# InputMicroproduct.net
KiCad netlist of a schematic drawn in Altium Designer
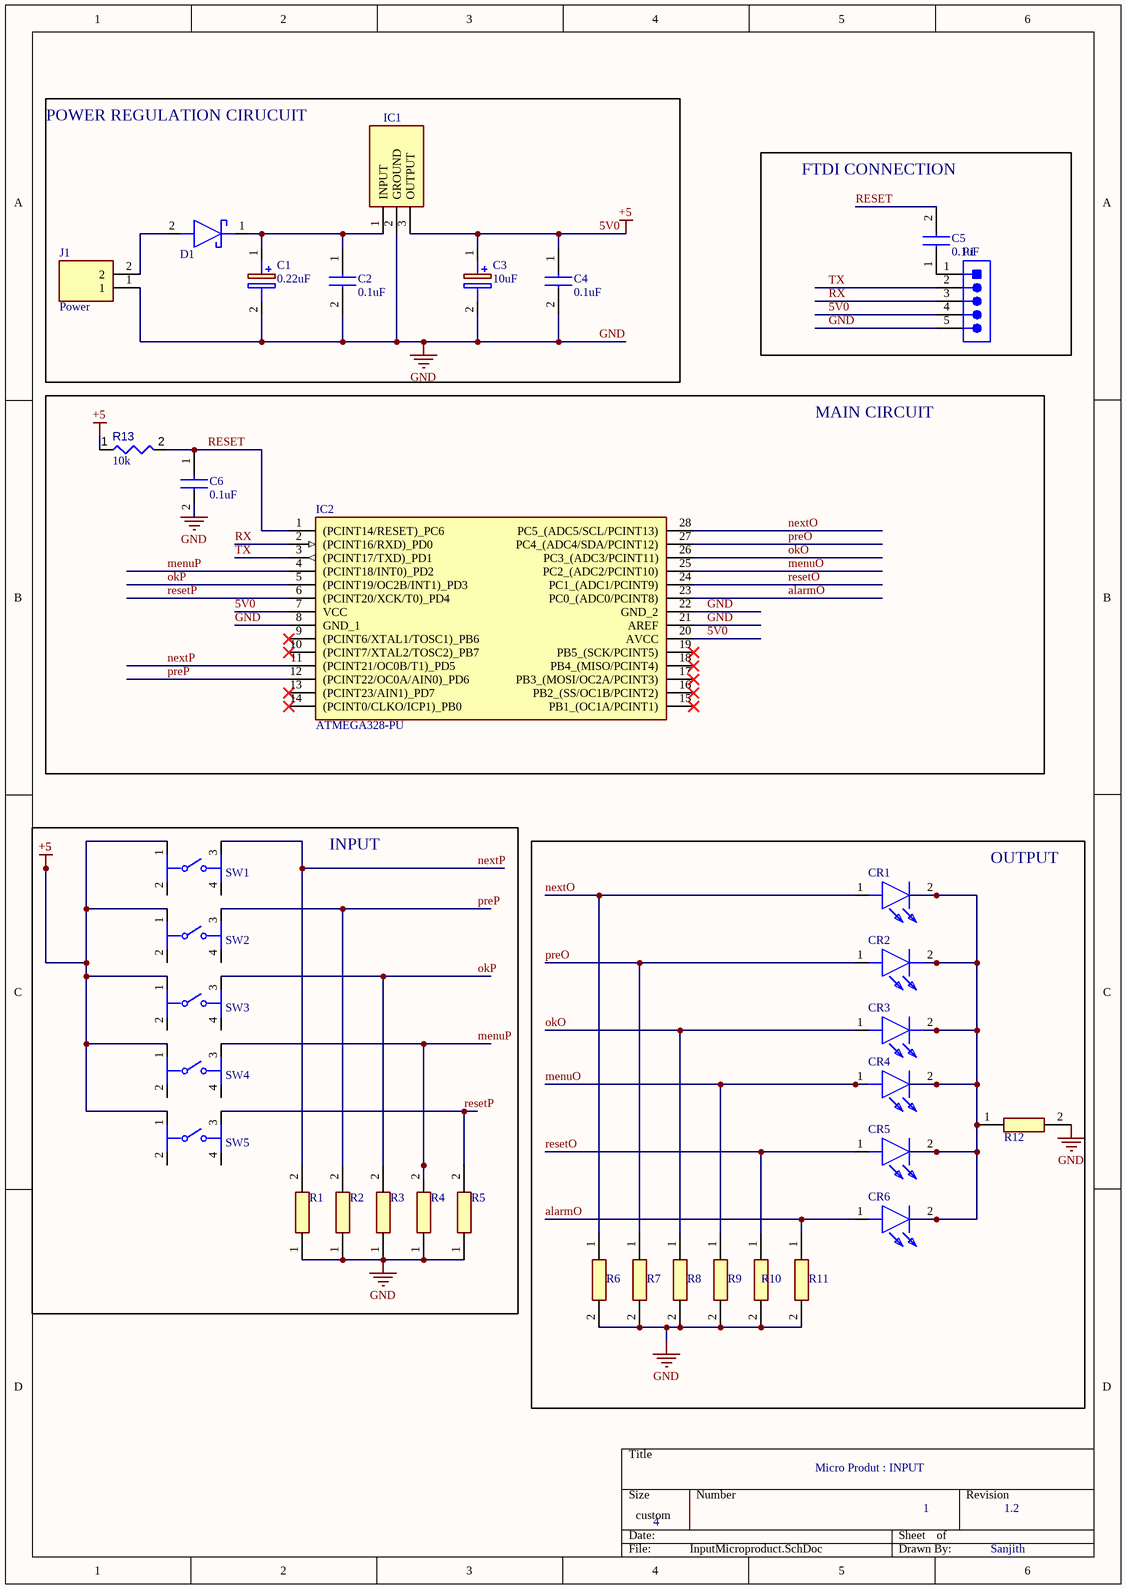
[diagram p0: InputMicroproduct.SchDoc]

(export (version "E")
  (design (tool "Eeschema 10.0.6"))
  (components
    (comp (ref "C1")
      (value "0.22uF")
      (footprint "SamacSys:CAPPRD200W52D500H1250")
      (description "Capacitor Polarised")
      (fields
        (field (name "MANUFACTURER_PART_NUMBER") "860010772002")
        (field (name "MOUSER PART NUMBER") "710-860010772002")
      )
      (libsource (lib "*") (part "860010772002"))
    )
    (comp (ref "C2")
      (value "0.1uF")
      (footprint "SamacSys:S104Z93Z5VL83L0R")
      (description "Capacitor")
      (fields
        (field (name "MANUFACTURER_PART_NUMBER") "S104Z93Z5VL83L0R")
        (field (name "MOUSER PART NUMBER") "594-S104Z93Z5VL83L0R")
      )
      (libsource (lib "*") (part "S104Z93Z5VL83L0R"))
    )
    (comp (ref "C3")
      (value "10uF")
      (footprint "SamacSys:CAPPRD200W55D500H1250")
      (description "Capacitor Polarised")
      (fields (field (name "MANUFACTURER_PART_NUMBER") "EEUFR1H100"))
      (libsource (lib "*") (part "EEUFR1H100"))
    )
    (comp (ref "C4")
      (value "0.1uF")
      (footprint "SamacSys:S104Z93Z5VL83L0R")
      (description "Capacitor")
      (fields
        (field (name "MANUFACTURER_PART_NUMBER") "S104Z93Z5VL83L0R")
        (field (name "MOUSER PART NUMBER") "594-S104Z93Z5VL83L0R")
      )
      (libsource (lib "*") (part "S104Z93Z5VL83L0R"))
    )
    (comp (ref "C5")
      (value "0.1uF")
      (footprint "SamacSys:S104Z93Z5VL83L0R")
      (description "Capacitor")
      (fields
        (field (name "MANUFACTURER_PART_NUMBER") "S104Z93Z5VL83L0R")
        (field (name "MOUSER PART NUMBER") "594-S104Z93Z5VL83L0R")
      )
      (libsource (lib "*") (part "S104Z93Z5VL83L0R"))
    )
    (comp (ref "C6")
      (value "0.1uF")
      (footprint "SamacSys:S104Z93Z5VL83L0R")
      (description "Capacitor")
      (fields
        (field (name "MANUFACTURER_PART_NUMBER") "S104Z93Z5VL83L0R")
        (field (name "MOUSER PART NUMBER") "594-S104Z93Z5VL83L0R")
      )
      (libsource (lib "*") (part "S104Z93Z5VL83L0R"))
    )
    (comp (ref "CR1")
      (value "SSL-LX5093SIC")
      (footprint "SamacSys:SSLLX5093SIC")
      (description "LED")
      (fields (field (name "MOUSER PART NUMBER") "696-SSL-LX5093SIC"))
      (libsource (lib "*") (part "SSL-LX5093SIC"))
    )
    (comp (ref "CR2")
      (value "SSL-LX5093SIC")
      (footprint "SamacSys:SSLLX5093SIC")
      (description "LED")
      (fields (field (name "MOUSER PART NUMBER") "696-SSL-LX5093SIC"))
      (libsource (lib "*") (part "SSL-LX5093SIC"))
    )
    (comp (ref "CR3")
      (value "SSL-LX5093SIC")
      (footprint "SamacSys:SSLLX5093SIC")
      (description "LED")
      (fields (field (name "MOUSER PART NUMBER") "696-SSL-LX5093SIC"))
      (libsource (lib "*") (part "SSL-LX5093SIC"))
    )
    (comp (ref "CR4")
      (value "SSL-LX5093SIC")
      (footprint "SamacSys:SSLLX5093SIC")
      (description "LED")
      (fields (field (name "MOUSER PART NUMBER") "696-SSL-LX5093SIC"))
      (libsource (lib "*") (part "SSL-LX5093SIC"))
    )
    (comp (ref "CR5")
      (value "SSL-LX5093SIC")
      (footprint "SamacSys:SSLLX5093SIC")
      (description "LED")
      (fields (field (name "MOUSER PART NUMBER") "696-SSL-LX5093SIC"))
      (libsource (lib "*") (part "SSL-LX5093SIC"))
    )
    (comp (ref "CR6")
      (value "SSL-LX5093SIC")
      (footprint "SamacSys:SSLLX5093SIC")
      (description "LED")
      (fields (field (name "MOUSER PART NUMBER") "696-SSL-LX5093SIC"))
      (libsource (lib "*") (part "SSL-LX5093SIC"))
    )
    (comp (ref "D1")
      (value "Protection Diode")
      (footprint "SamacSys:DIOAD950W60L350D150")
      (description "Schottky Diode")
      (fields
        (field (name "MANUFACTURER_PART_NUMBER") "SD103A-TR")
        (field (name "MOUSER PART NUMBER") "625-SD103A")
      )
      (libsource (lib "*") (part "SD103A-TR"))
    )
    (comp (ref "IC1")
      (value "Power Regulator")
      (footprint "SamacSys:TO255P460X1020X2008-3P")
      (description "Integrated Circuit")
      (fields
        (field (name "MANUFACTURER_PART_NUMBER") "L7805CV")
        (field (name "MOUSER PART NUMBER") "511-L7805CV")
      )
      (libsource (lib "*") (part "L7805CV"))
    )
    (comp (ref "IC2")
      (value "ATMEGA328-PU")
      (footprint "SamacSys:DIP1016W53P254L3468H457Q28N")
      (description "Integrated Circuit")
      (fields (field (name "MOUSER PART NUMBER") "556-ATMEGA328-PU"))
      (libsource (lib "*") (part "ATMEGA328-PU"))
    )
    (comp (ref "J1")
      (value "1546215-2")
      (footprint "SamacSys:15462152")
      (description "Connector - Two pin (Power)")
      (fields (field (name "MOUSER PART NUMBER") "571-1546215-2") (field (name "TEXT") "Power"))
      (libsource (lib "*") (part "1546215-2"))
    )
    (comp (ref "P1")
      (value "77311-462K05LF")
      (footprint "FCI-77311-5_V")
      (fields (field (name "MANUFACTURER") "FCI Electronics"))
      (libsource (lib "University of Moratuwa") (part "CN-1P-M-R5"))
    )
    (comp (ref "R1")
      (value "CFR-25JB-52-1K2")
      (footprint "SamacSys:RESAD1590W60L630D240")
      (description "Pulldown Resistor")
      (fields (field (name "MOUSER PART NUMBER") "603-CFR-25JB-52-1K2"))
      (libsource (lib "") (part "CFR-25JB-52-1K2_1"))
    )
    (comp (ref "R2")
      (value "CFR-25JB-52-1K2")
      (footprint "SamacSys:RESAD1590W60L630D240")
      (description "Pulldown Resistor")
      (fields (field (name "MOUSER PART NUMBER") "603-CFR-25JB-52-1K2"))
      (libsource (lib "") (part "CFR-25JB-52-1K2_1"))
    )
    (comp (ref "R3")
      (value "CFR-25JB-52-1K2")
      (footprint "SamacSys:RESAD1590W60L630D240")
      (description "Pulldown Resistor")
      (fields (field (name "MOUSER PART NUMBER") "603-CFR-25JB-52-1K2"))
      (libsource (lib "") (part "CFR-25JB-52-1K2_1"))
    )
    (comp (ref "R4")
      (value "CFR-25JB-52-1K2")
      (footprint "SamacSys:RESAD1590W60L630D240")
      (description "Pulldown Resistor")
      (fields (field (name "MOUSER PART NUMBER") "603-CFR-25JB-52-1K2"))
      (libsource (lib "") (part "CFR-25JB-52-1K2_1"))
    )
    (comp (ref "R5")
      (value "CFR-25JB-52-1K2")
      (footprint "SamacSys:RESAD1590W60L630D240")
      (description "Pulldown Resistor")
      (fields (field (name "MOUSER PART NUMBER") "603-CFR-25JB-52-1K2"))
      (libsource (lib "") (part "CFR-25JB-52-1K2_1"))
    )
    (comp (ref "R6")
      (value "CFR-25JB-52-1K2")
      (footprint "SamacSys:RESAD1590W60L630D240")
      (description "Pulldown Resistor")
      (fields (field (name "MOUSER PART NUMBER") "603-CFR-25JB-52-1K2"))
      (libsource (lib "*") (part "CFR-25JB-52-1K2"))
    )
    (comp (ref "R7")
      (value "CFR-25JB-52-1K2")
      (footprint "SamacSys:RESAD1590W60L630D240")
      (description "Pulldown Resistor")
      (fields (field (name "MOUSER PART NUMBER") "603-CFR-25JB-52-1K2"))
      (libsource (lib "*") (part "CFR-25JB-52-1K2"))
    )
    (comp (ref "R8")
      (value "CFR-25JB-52-1K2")
      (footprint "SamacSys:RESAD1590W60L630D240")
      (description "Pulldown Resistor")
      (fields (field (name "MOUSER PART NUMBER") "603-CFR-25JB-52-1K2"))
      (libsource (lib "*") (part "CFR-25JB-52-1K2"))
    )
    (comp (ref "R9")
      (value "CFR-25JB-52-1K2")
      (footprint "SamacSys:RESAD1590W60L630D240")
      (description "Pulldown Resistor")
      (fields (field (name "MOUSER PART NUMBER") "603-CFR-25JB-52-1K2"))
      (libsource (lib "*") (part "CFR-25JB-52-1K2"))
    )
    (comp (ref "R10")
      (value "CFR-25JB-52-1K2")
      (footprint "SamacSys:RESAD1590W60L630D240")
      (description "Pulldown Resistor")
      (fields (field (name "MOUSER PART NUMBER") "603-CFR-25JB-52-1K2"))
      (libsource (lib "*") (part "CFR-25JB-52-1K2"))
    )
    (comp (ref "R11")
      (value "CFR-25JB-52-1K2")
      (footprint "SamacSys:RESAD1590W60L630D240")
      (description "Pulldown Resistor")
      (fields (field (name "MOUSER PART NUMBER") "603-CFR-25JB-52-1K2"))
      (libsource (lib "*") (part "CFR-25JB-52-1K2"))
    )
    (comp (ref "R12")
      (value "CFR-25JB-52-1K2")
      (footprint "SamacSys:RESAD1590W60L630D240")
      (description "Pulldown Resistor")
      (fields (field (name "MOUSER PART NUMBER") "603-CFR-25JB-52-1K2"))
      (libsource (lib "") (part "CFR-25JB-52-1K2_2"))
    )
    (comp (ref "R13")
      (value "10k")
      (footprint "RESA60-630X240")
      (description "Axial Resistor, 10 KOhm, +/- 1%, 0.25 W, -55 to 155 degC, 2-Pin THD, RoHS, Bulk")
      (fields (field (name "POWER") "250mW") (field (name "MANUFACTURER") "Yageo"))
      (libsource (lib "University of Moratuwa") (part "RES-2"))
    )
    (comp (ref "SW1")
      (value "3-1825910-1")
      (footprint "FP-3-1825910-1-MFG")
      (description "Switch Tactile OFF (ON) SPST Round Button PC Pins 0.05A 24VDC 100000Cycles 1.57N Thru-Hole")
      (fields (field (name "MANUFACTURER") "TE Connectivity"))
      (libsource (lib "Altium Content Vault") (part "b8895f3f4cefb76e1819d2863dba89b"))
    )
    (comp (ref "SW2")
      (value "3-1825910-1")
      (footprint "FP-3-1825910-1-MFG")
      (description "Switch Tactile OFF (ON) SPST Round Button PC Pins 0.05A 24VDC 100000Cycles 1.57N Thru-Hole")
      (fields (field (name "MANUFACTURER") "TE Connectivity"))
      (libsource (lib "Altium Content Vault") (part "b8895f3f4cefb76e1819d2863dba89b"))
    )
    (comp (ref "SW3")
      (value "3-1825910-1")
      (footprint "FP-3-1825910-1-MFG")
      (description "Switch Tactile OFF (ON) SPST Round Button PC Pins 0.05A 24VDC 100000Cycles 1.57N Thru-Hole")
      (fields (field (name "MANUFACTURER") "TE Connectivity"))
      (libsource (lib "Altium Content Vault") (part "b8895f3f4cefb76e1819d2863dba89b"))
    )
    (comp (ref "SW4")
      (value "3-1825910-1")
      (footprint "FP-3-1825910-1-MFG")
      (description "Switch Tactile OFF (ON) SPST Round Button PC Pins 0.05A 24VDC 100000Cycles 1.57N Thru-Hole")
      (fields (field (name "MANUFACTURER") "TE Connectivity"))
      (libsource (lib "Altium Content Vault") (part "b8895f3f4cefb76e1819d2863dba89b"))
    )
    (comp (ref "SW5")
      (value "3-1825910-1")
      (footprint "FP-3-1825910-1-MFG")
      (description "Switch Tactile OFF (ON) SPST Round Button PC Pins 0.05A 24VDC 100000Cycles 1.57N Thru-Hole")
      (fields (field (name "MANUFACTURER") "TE Connectivity"))
      (libsource (lib "Altium Content Vault") (part "b8895f3f4cefb76e1819d2863dba89b"))
    )
  )
  (nets
    (net (code "1") (name "+5") (class "Default")
      (node (ref "C3") (pin "1") (pinfunction "+_1") (pintype "passive"))
      (node (ref "C4") (pin "1") (pinfunction "1_1") (pintype "passive"))
      (node (ref "IC1") (pin "3") (pinfunction "OUTPUT_3") (pintype "passive"))
      (node (ref "IC2") (pin "20") (pinfunction "AVCC_20") (pintype "power_in"))
      (node (ref "IC2") (pin "7") (pinfunction "VCC_7") (pintype "power_in"))
      (node (ref "P1") (pin "4") (pinfunction "VCC_4") (pintype "passive"))
      (node (ref "R13") (pin "1") (pinfunction "1_1") (pintype "passive"))
      (node (ref "SW1") (pin "1") (pinfunction "1_1") (pintype "passive"))
      (node (ref "SW2") (pin "1") (pinfunction "1_1") (pintype "passive"))
      (node (ref "SW3") (pin "1") (pinfunction "1_1") (pintype "passive"))
      (node (ref "SW4") (pin "1") (pinfunction "1_1") (pintype "passive"))
      (node (ref "SW5") (pin "1") (pinfunction "1_1") (pintype "passive"))
    )
    (net (code "2") (name "/RESET") (class "Default")
      (node (ref "C5") (pin "2") (pinfunction "2_2") (pintype "passive"))
      (node (ref "C6") (pin "1") (pinfunction "1_1") (pintype "passive"))
      (node (ref "IC2") (pin "1") (pinfunction "(PCINT14/RESET)_PC6_1") (pintype "passive"))
      (node (ref "R13") (pin "2") (pinfunction "2_2") (pintype "passive"))
    )
    (net (code "3") (name "/RX") (class "Default")
      (node (ref "IC2") (pin "2") (pinfunction "(PCINT16/RXD)_PD0_2") (pintype "input"))
      (node (ref "P1") (pin "3") (pinfunction "TXO_3") (pintype "passive"))
    )
    (net (code "4") (name "/TX") (class "Default")
      (node (ref "IC2") (pin "3") (pinfunction "(PCINT17/TXD)_PD1_3") (pintype "output"))
      (node (ref "P1") (pin "2") (pinfunction "RXI_2") (pintype "passive"))
    )
    (net (code "5") (name "/alarmO") (class "Default")
      (node (ref "CR6") (pin "1") (pinfunction "A_1") (pintype "passive"))
      (node (ref "IC2") (pin "23") (pinfunction "PC0_(ADC0/PCINT8)_23") (pintype "passive"))
      (node (ref "R11") (pin "1") (pinfunction "1_1") (pintype "passive"))
    )
    (net (code "6") (name "/menuO") (class "Default")
      (node (ref "CR4") (pin "1") (pinfunction "A_1") (pintype "passive"))
      (node (ref "IC2") (pin "25") (pinfunction "PC2_(ADC2/PCINT10)_25") (pintype "passive"))
      (node (ref "R9") (pin "1") (pinfunction "1_1") (pintype "passive"))
    )
    (net (code "7") (name "/menuP") (class "Default")
      (node (ref "IC2") (pin "4") (pinfunction "(PCINT18/INT0)_PD2_4") (pintype "passive"))
      (node (ref "R4") (pin "2") (pinfunction "2_2") (pintype "passive"))
      (node (ref "SW4") (pin "3") (pinfunction "3_3") (pintype "passive"))
    )
    (net (code "8") (name "/nextO") (class "Default")
      (node (ref "CR1") (pin "1") (pinfunction "A_1") (pintype "passive"))
      (node (ref "IC2") (pin "28") (pinfunction "PC5_(ADC5/SCL/PCINT13)_28") (pintype "passive"))
      (node (ref "R6") (pin "1") (pinfunction "1_1") (pintype "passive"))
    )
    (net (code "9") (name "/nextP") (class "Default")
      (node (ref "IC2") (pin "11") (pinfunction "(PCINT21/OC0B/T1)_PD5_11") (pintype "passive"))
      (node (ref "R1") (pin "2") (pinfunction "2_2") (pintype "passive"))
      (node (ref "SW1") (pin "3") (pinfunction "3_3") (pintype "passive"))
    )
    (net (code "10") (name "/okO") (class "Default")
      (node (ref "CR3") (pin "1") (pinfunction "A_1") (pintype "passive"))
      (node (ref "IC2") (pin "26") (pinfunction "PC3_(ADC3/PCINT11)_26") (pintype "passive"))
      (node (ref "R8") (pin "1") (pinfunction "1_1") (pintype "passive"))
    )
    (net (code "11") (name "/okP") (class "Default")
      (node (ref "IC2") (pin "5") (pinfunction "(PCINT19/OC2B/INT1)_PD3_5") (pintype "passive"))
      (node (ref "R3") (pin "2") (pinfunction "2_2") (pintype "passive"))
      (node (ref "SW3") (pin "3") (pinfunction "3_3") (pintype "passive"))
    )
    (net (code "12") (name "/preO") (class "Default")
      (node (ref "CR2") (pin "1") (pinfunction "A_1") (pintype "passive"))
      (node (ref "IC2") (pin "27") (pinfunction "PC4_(ADC4/SDA/PCINT12)_27") (pintype "passive"))
      (node (ref "R7") (pin "1") (pinfunction "1_1") (pintype "passive"))
    )
    (net (code "13") (name "/preP") (class "Default")
      (node (ref "IC2") (pin "12") (pinfunction "(PCINT22/OC0A/AIN0)_PD6_12") (pintype "passive"))
      (node (ref "R2") (pin "2") (pinfunction "2_2") (pintype "passive"))
      (node (ref "SW2") (pin "3") (pinfunction "3_3") (pintype "passive"))
    )
    (net (code "14") (name "/resetO") (class "Default")
      (node (ref "CR5") (pin "1") (pinfunction "A_1") (pintype "passive"))
      (node (ref "IC2") (pin "24") (pinfunction "PC1_(ADC1/PCINT9)_24") (pintype "passive"))
      (node (ref "R10") (pin "1") (pinfunction "1_1") (pintype "passive"))
    )
    (net (code "15") (name "/resetP") (class "Default")
      (node (ref "IC2") (pin "6") (pinfunction "(PCINT20/XCK/T0)_PD4_6") (pintype "passive"))
      (node (ref "R5") (pin "2") (pinfunction "2_2") (pintype "passive"))
      (node (ref "SW5") (pin "3") (pinfunction "3_3") (pintype "passive"))
    )
    (net (code "16") (name "GND") (class "Default")
      (node (ref "C1") (pin "2") (pinfunction "-_2") (pintype "passive"))
      (node (ref "C2") (pin "2") (pinfunction "2_2") (pintype "passive"))
      (node (ref "C3") (pin "2") (pinfunction "-_2") (pintype "passive"))
      (node (ref "C4") (pin "2") (pinfunction "2_2") (pintype "passive"))
      (node (ref "C6") (pin "2") (pinfunction "2_2") (pintype "passive"))
      (node (ref "IC1") (pin "2") (pinfunction "GROUND_2") (pintype "passive"))
      (node (ref "IC2") (pin "21") (pinfunction "AREF_21") (pintype "passive"))
      (node (ref "IC2") (pin "22") (pinfunction "GND_2_22") (pintype "power_in"))
      (node (ref "IC2") (pin "8") (pinfunction "GND_1_8") (pintype "power_in"))
      (node (ref "J1") (pin "1") (pinfunction "1_1") (pintype "passive"))
      (node (ref "P1") (pin "5") (pinfunction "CTS_5") (pintype "passive"))
      (node (ref "R1") (pin "1") (pinfunction "1_1") (pintype "passive"))
      (node (ref "R10") (pin "2") (pinfunction "2_2") (pintype "passive"))
      (node (ref "R11") (pin "2") (pinfunction "2_2") (pintype "passive"))
      (node (ref "R12") (pin "2") (pinfunction "2_2") (pintype "passive"))
      (node (ref "R2") (pin "1") (pinfunction "1_1") (pintype "passive"))
      (node (ref "R3") (pin "1") (pinfunction "1_1") (pintype "passive"))
      (node (ref "R4") (pin "1") (pinfunction "1_1") (pintype "passive"))
      (node (ref "R5") (pin "1") (pinfunction "1_1") (pintype "passive"))
      (node (ref "R6") (pin "2") (pinfunction "2_2") (pintype "passive"))
      (node (ref "R7") (pin "2") (pinfunction "2_2") (pintype "passive"))
      (node (ref "R8") (pin "2") (pinfunction "2_2") (pintype "passive"))
      (node (ref "R9") (pin "2") (pinfunction "2_2") (pintype "passive"))
    )
    (net (code "17") (name "Net-(C1-+)") (class "Default")
      (node (ref "C1") (pin "1") (pinfunction "+_1") (pintype "passive"))
      (node (ref "C2") (pin "1") (pinfunction "1_1") (pintype "passive"))
      (node (ref "D1") (pin "1") (pinfunction "K_1") (pintype "passive"))
      (node (ref "IC1") (pin "1") (pinfunction "INPUT_1") (pintype "passive"))
    )
    (net (code "18") (name "Net-(CR1-K)") (class "Default")
      (node (ref "CR1") (pin "2") (pinfunction "K_2") (pintype "passive"))
      (node (ref "CR2") (pin "2") (pinfunction "K_2") (pintype "passive"))
      (node (ref "CR3") (pin "2") (pinfunction "K_2") (pintype "passive"))
      (node (ref "CR4") (pin "2") (pinfunction "K_2") (pintype "passive"))
      (node (ref "CR5") (pin "2") (pinfunction "K_2") (pintype "passive"))
      (node (ref "CR6") (pin "2") (pinfunction "K_2") (pintype "passive"))
      (node (ref "R12") (pin "1") (pinfunction "1_1") (pintype "passive"))
    )
    (net (code "19") (name "Net-(D1-A)") (class "Default")
      (node (ref "D1") (pin "2") (pinfunction "A_2") (pintype "passive"))
      (node (ref "J1") (pin "2") (pinfunction "2_2") (pintype "passive"))
    )
    (net (code "20") (name "Net-(P1-DTR)") (class "Default")
      (node (ref "C5") (pin "1") (pinfunction "1_1") (pintype "passive"))
      (node (ref "P1") (pin "1") (pinfunction "DTR_1") (pintype "passive"))
    )
    (net (code "21") (name "unconnected-(IC2-(PCINT0{slash}CLKO{slash}ICP1)_PB0-Pad14)") (class "Default")
      (node (ref "IC2") (pin "14") (pinfunction "(PCINT0/CLKO/ICP1)_PB0_14") (pintype "passive+no_connect"))
    )
    (net (code "22") (name "unconnected-(IC2-(PCINT6{slash}XTAL1{slash}TOSC1)_PB6-Pad9)") (class "Default")
      (node (ref "IC2") (pin "9") (pinfunction "(PCINT6/XTAL1/TOSC1)_PB6_9") (pintype "passive+no_connect"))
    )
    (net (code "23") (name "unconnected-(IC2-(PCINT7{slash}XTAL2{slash}TOSC2)_PB7-Pad10)") (class "Default")
      (node (ref "IC2") (pin "10") (pinfunction "(PCINT7/XTAL2/TOSC2)_PB7_10") (pintype "passive+no_connect"))
    )
    (net (code "24") (name "unconnected-(IC2-(PCINT23{slash}AIN1)_PD7-Pad13)") (class "Default")
      (node (ref "IC2") (pin "13") (pinfunction "(PCINT23/AIN1)_PD7_13") (pintype "passive+no_connect"))
    )
    (net (code "25") (name "unconnected-(IC2-PB1_(OC1A{slash}PCINT1)-Pad15)") (class "Default")
      (node (ref "IC2") (pin "15") (pinfunction "PB1_(OC1A/PCINT1)_15") (pintype "passive+no_connect"))
    )
    (net (code "26") (name "unconnected-(IC2-PB2_(SS{slash}OC1B{slash}PCINT2)-Pad16)") (class "Default")
      (node (ref "IC2") (pin "16") (pinfunction "PB2_(SS/OC1B/PCINT2)_16") (pintype "passive+no_connect"))
    )
    (net (code "27") (name "unconnected-(IC2-PB3_(MOSI{slash}OC2A{slash}PCINT3)-Pad17)") (class "Default")
      (node (ref "IC2") (pin "17") (pinfunction "PB3_(MOSI/OC2A/PCINT3)_17") (pintype "passive+no_connect"))
    )
    (net (code "28") (name "unconnected-(IC2-PB4_(MISO{slash}PCINT4)-Pad18)") (class "Default")
      (node (ref "IC2") (pin "18") (pinfunction "PB4_(MISO/PCINT4)_18") (pintype "passive+no_connect"))
    )
    (net (code "29") (name "unconnected-(IC2-PB5_(SCK{slash}PCINT5)-Pad19)") (class "Default")
      (node (ref "IC2") (pin "19") (pinfunction "PB5_(SCK/PCINT5)_19") (pintype "passive+no_connect"))
    )
    (net (code "30") (name "unconnected-(SW1-Pad2)") (class "Default")
      (node (ref "SW1") (pin "2") (pinfunction "2_2") (pintype "passive"))
    )
    (net (code "31") (name "unconnected-(SW1-Pad4)") (class "Default")
      (node (ref "SW1") (pin "4") (pinfunction "4_4") (pintype "passive"))
    )
    (net (code "32") (name "unconnected-(SW2-Pad2)") (class "Default")
      (node (ref "SW2") (pin "2") (pinfunction "2_2") (pintype "passive"))
    )
    (net (code "33") (name "unconnected-(SW2-Pad4)") (class "Default")
      (node (ref "SW2") (pin "4") (pinfunction "4_4") (pintype "passive"))
    )
    (net (code "34") (name "unconnected-(SW3-Pad2)") (class "Default")
      (node (ref "SW3") (pin "2") (pinfunction "2_2") (pintype "passive"))
    )
    (net (code "35") (name "unconnected-(SW3-Pad4)") (class "Default")
      (node (ref "SW3") (pin "4") (pinfunction "4_4") (pintype "passive"))
    )
    (net (code "36") (name "unconnected-(SW4-Pad2)") (class "Default")
      (node (ref "SW4") (pin "2") (pinfunction "2_2") (pintype "passive"))
    )
    (net (code "37") (name "unconnected-(SW4-Pad4)") (class "Default")
      (node (ref "SW4") (pin "4") (pinfunction "4_4") (pintype "passive"))
    )
    (net (code "38") (name "unconnected-(SW5-Pad2)") (class "Default")
      (node (ref "SW5") (pin "2") (pinfunction "2_2") (pintype "passive"))
    )
    (net (code "39") (name "unconnected-(SW5-Pad4)") (class "Default")
      (node (ref "SW5") (pin "4") (pinfunction "4_4") (pintype "passive"))
    )
  )
)
